# 10-TEST_PORT.net
KiCad netlist of a schematic drawn in Altium Designer
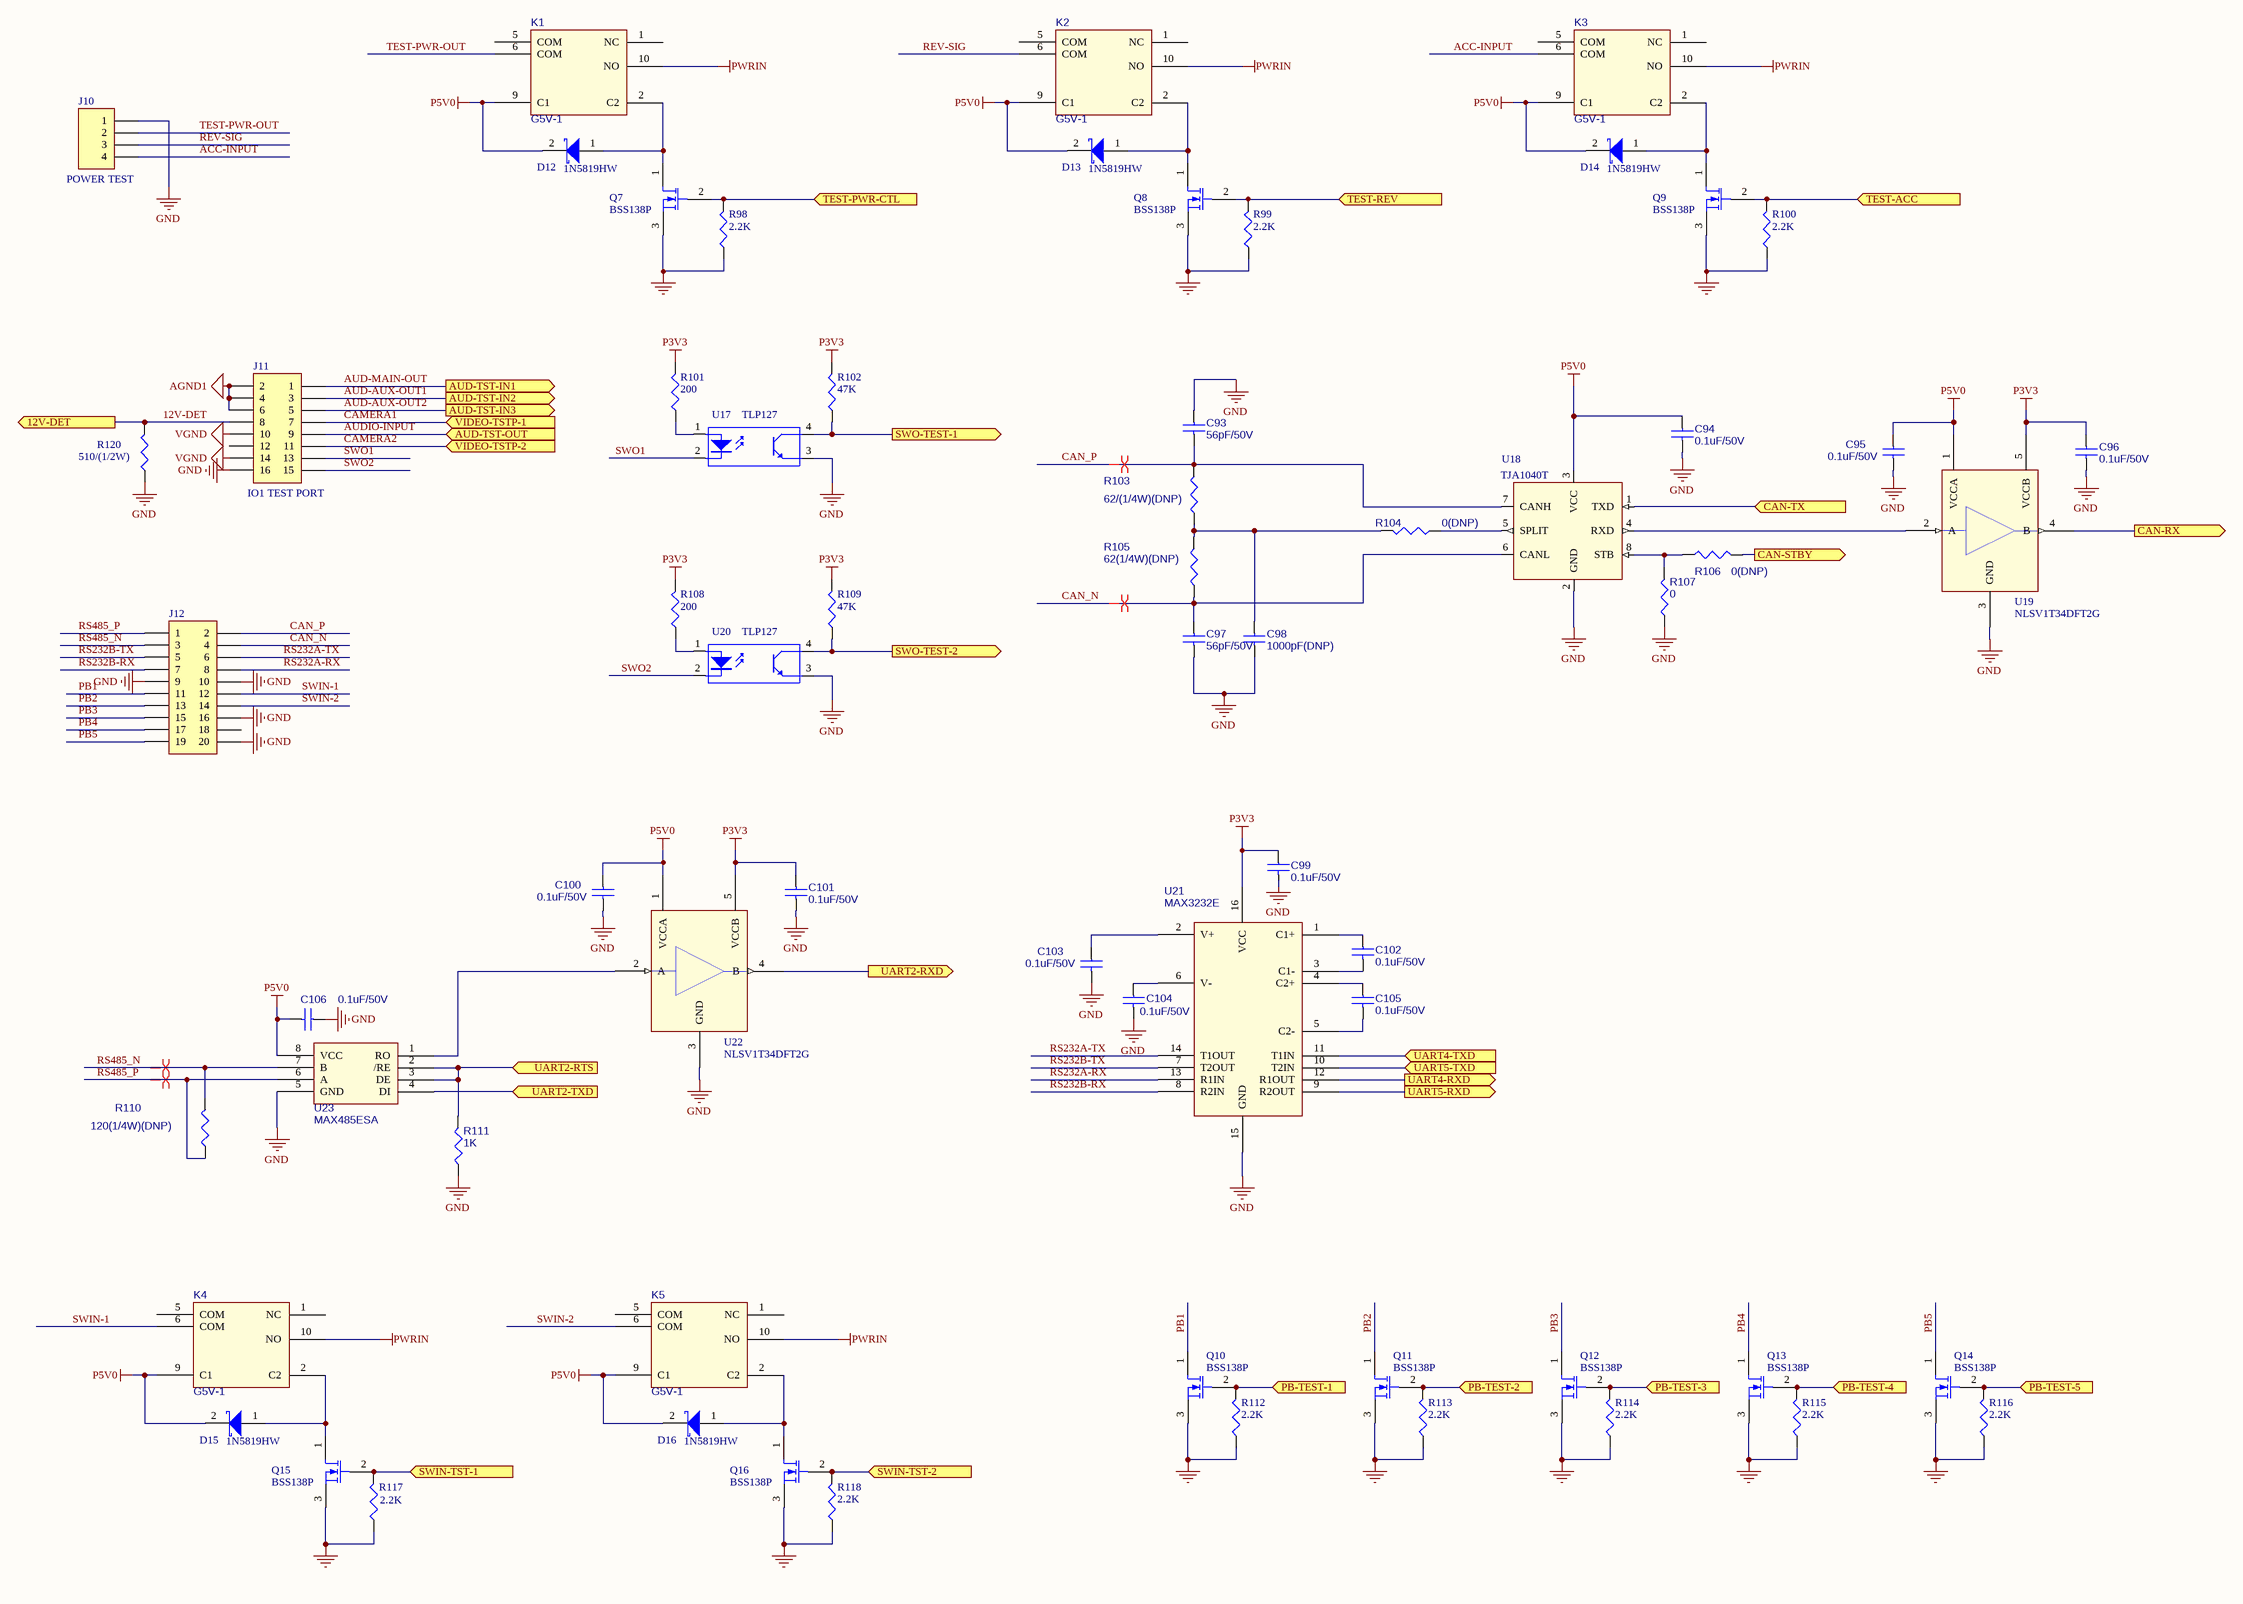
[diagram p0: 10-TEST_PORT.SchDoc]

(export (version "E")
  (design (tool "Eeschema 10.0.6"))
  (components
    (comp (ref "C93") (value "56pF/50V") (libsource (lib "*") (part "P_CAP NP")))
    (comp (ref "C94") (value "0.1uF/50V") (libsource (lib "*") (part "P_CAP NP")))
    (comp (ref "C95") (value "0.1uF/50V") (libsource (lib "*") (part "P_CAP NP")))
    (comp (ref "C96") (value "0.1uF/50V") (libsource (lib "*") (part "P_CAP NP")))
    (comp (ref "C97") (value "56pF/50V") (libsource (lib "*") (part "P_CAP NP")))
    (comp (ref "C98") (value "1000pF(DNP)") (libsource (lib "*") (part "P_CAP NP")))
    (comp (ref "C99") (value "0.1uF/50V") (libsource (lib "*") (part "CAP")))
    (comp (ref "C100") (value "0.1uF/50V") (libsource (lib "*") (part "P_CAP NP")))
    (comp (ref "C101") (value "0.1uF/50V") (libsource (lib "*") (part "P_CAP NP")))
    (comp (ref "C102") (value "0.1uF/50V") (libsource (lib "*") (part "CAP")))
    (comp (ref "C103") (value "0.1uF/50V") (libsource (lib "*") (part "CAP")))
    (comp (ref "C104") (value "0.1uF/50V") (libsource (lib "*") (part "CAP")))
    (comp (ref "C105") (value "0.1uF/50V") (libsource (lib "*") (part "CAP")))
    (comp (ref "C106")
      (value "0.1uF/50V")
      (fields (field (name "PART NUMBER") "SE132225K8L"))
      (libsource (lib "*") (part "P_CAP NP"))
    )
    (comp (ref "D12")
      (value "1N5819HW")
      (footprint "1N5819")
      (description "Schottky Rectifier")
      (libsource (lib "Miscellaneous Devices") (part "Diode 11DQ03"))
    )
    (comp (ref "D13")
      (value "1N5819HW")
      (footprint "1N5819")
      (description "Schottky Rectifier")
      (libsource (lib "Miscellaneous Devices") (part "Diode 11DQ03"))
    )
    (comp (ref "D14")
      (value "1N5819HW")
      (footprint "1N5819")
      (description "Schottky Rectifier")
      (libsource (lib "Miscellaneous Devices") (part "Diode 11DQ03"))
    )
    (comp (ref "D15")
      (value "1N5819HW")
      (footprint "1N5819")
      (description "Schottky Rectifier")
      (libsource (lib "Miscellaneous Devices") (part "Diode 11DQ03"))
    )
    (comp (ref "D16")
      (value "1N5819HW")
      (footprint "1N5819")
      (description "Schottky Rectifier")
      (libsource (lib "Miscellaneous Devices") (part "Diode 11DQ03"))
    )
    (comp (ref "J10")
      (value "POWER TEST")
      (footprint "3030WR-S-2*2P")
      (description "Header, 4-Pin")
      (fields (field (name "PUBLISHER") "Altium Limited"))
      (libsource (lib "Miscellaneous Connectors") (part "Header 4"))
    )
    (comp (ref "J11")
      (value "IO1 TEST PORT")
      (footprint "3030WR-S-2*8P")
      (description "Header, 8-Pin, Dual row")
      (fields (field (name "PUBLISHER") "Altium Limited"))
      (libsource (lib "Miscellaneous Connectors") (part "Header 8X2"))
    )
    (comp (ref "J12")
      (value "Header 10X2")
      (footprint "3030WR-S-2*10P")
      (description "Header, 10-Pin, Dual row")
      (fields (field (name "PUBLISHER") "Altium Limited"))
      (libsource (lib "Miscellaneous Connectors") (part "Header 10X2"))
    )
    (comp (ref "K1") (value "G5V-1") (libsource (lib "*") (part "G5V-1_0")))
    (comp (ref "K2") (value "G5V-1") (libsource (lib "*") (part "G5V-1_0")))
    (comp (ref "K3") (value "G5V-1") (libsource (lib "*") (part "G5V-1_0")))
    (comp (ref "K4") (value "G5V-1") (libsource (lib "*") (part "G5V-1_0")))
    (comp (ref "K5") (value "G5V-1") (libsource (lib "*") (part "G5V-1_0")))
    (comp (ref "Q7")
      (value "BSS138P")
      (footprint "NPN")
      (description "N-Channel MOSFET")
      (fields (field (name "PUBLISHER") "Altium Limited"))
      (libsource (lib "Miscellaneous Devices") (part "MOSFET-N"))
    )
    (comp (ref "Q8")
      (value "BSS138P")
      (footprint "NPN")
      (description "N-Channel MOSFET")
      (fields (field (name "PUBLISHER") "Altium Limited"))
      (libsource (lib "Miscellaneous Devices") (part "MOSFET-N"))
    )
    (comp (ref "Q9")
      (value "BSS138P")
      (footprint "NPN")
      (description "N-Channel MOSFET")
      (fields (field (name "PUBLISHER") "Altium Limited"))
      (libsource (lib "Miscellaneous Devices") (part "MOSFET-N"))
    )
    (comp (ref "Q10")
      (value "BSS138P")
      (footprint "NPN")
      (description "N-Channel MOSFET")
      (fields (field (name "PUBLISHER") "Altium Limited"))
      (libsource (lib "Miscellaneous Devices") (part "MOSFET-N"))
    )
    (comp (ref "Q11")
      (value "BSS138P")
      (footprint "NPN")
      (description "N-Channel MOSFET")
      (fields (field (name "PUBLISHER") "Altium Limited"))
      (libsource (lib "Miscellaneous Devices") (part "MOSFET-N"))
    )
    (comp (ref "Q12")
      (value "BSS138P")
      (footprint "NPN")
      (description "N-Channel MOSFET")
      (fields (field (name "PUBLISHER") "Altium Limited"))
      (libsource (lib "Miscellaneous Devices") (part "MOSFET-N"))
    )
    (comp (ref "Q13")
      (value "BSS138P")
      (footprint "NPN")
      (description "N-Channel MOSFET")
      (fields (field (name "PUBLISHER") "Altium Limited"))
      (libsource (lib "Miscellaneous Devices") (part "MOSFET-N"))
    )
    (comp (ref "Q14")
      (value "BSS138P")
      (footprint "NPN")
      (description "N-Channel MOSFET")
      (fields (field (name "PUBLISHER") "Altium Limited"))
      (libsource (lib "Miscellaneous Devices") (part "MOSFET-N"))
    )
    (comp (ref "Q15")
      (value "BSS138P")
      (footprint "NPN")
      (description "N-Channel MOSFET")
      (fields (field (name "PUBLISHER") "Altium Limited"))
      (libsource (lib "Miscellaneous Devices") (part "MOSFET-N"))
    )
    (comp (ref "Q16")
      (value "BSS138P")
      (footprint "NPN")
      (description "N-Channel MOSFET")
      (fields (field (name "PUBLISHER") "Altium Limited"))
      (libsource (lib "Miscellaneous Devices") (part "MOSFET-N"))
    )
    (comp (ref "R98")
      (value "2.2K")
      (footprint "0402")
      (description "Resistor")
      (fields (field (name "PUBLISHER") "Altium Limited"))
      (libsource (lib "Miscellaneous Devices") (part "Res3"))
    )
    (comp (ref "R99")
      (value "2.2K")
      (footprint "0402")
      (description "Resistor")
      (fields (field (name "PUBLISHER") "Altium Limited"))
      (libsource (lib "Miscellaneous Devices") (part "Res3"))
    )
    (comp (ref "R100")
      (value "2.2K")
      (footprint "0402")
      (description "Resistor")
      (fields (field (name "PUBLISHER") "Altium Limited"))
      (libsource (lib "Miscellaneous Devices") (part "Res3"))
    )
    (comp (ref "R101")
      (value "200")
      (footprint "0402")
      (description "Resistor")
      (fields (field (name "PUBLISHER") "Altium Limited"))
      (libsource (lib "Miscellaneous Devices") (part "Res3"))
    )
    (comp (ref "R102")
      (value "47K")
      (footprint "0402")
      (description "Resistor")
      (fields (field (name "PUBLISHER") "Altium Limited"))
      (libsource (lib "Miscellaneous Devices") (part "Res3"))
    )
    (comp (ref "R103") (value "62/(1/4W)(DNP)") (footprint "1206") (libsource (lib "*") (part "P_R")))
    (comp (ref "R104") (value "0(DNP)") (footprint "0402") (libsource (lib "*") (part "P_R")))
    (comp (ref "R105") (value "62(1/4W)(DNP)") (footprint "1206") (libsource (lib "*") (part "P_R")))
    (comp (ref "R106") (value "0(DNP)") (footprint "0402") (libsource (lib "*") (part "P_R")))
    (comp (ref "R107") (value "0") (footprint "0402") (libsource (lib "*") (part "P_R")))
    (comp (ref "R108")
      (value "200")
      (footprint "0402")
      (description "Resistor")
      (fields (field (name "PUBLISHER") "Altium Limited"))
      (libsource (lib "Miscellaneous Devices") (part "Res3"))
    )
    (comp (ref "R109")
      (value "47K")
      (footprint "0402")
      (description "Resistor")
      (fields (field (name "PUBLISHER") "Altium Limited"))
      (libsource (lib "Miscellaneous Devices") (part "Res3"))
    )
    (comp (ref "R110")
      (value "120(1/4W)(DNP)")
      (fields (field (name "PART NUMBER") "SD02810028L"))
      (libsource (lib "*") (part "R"))
    )
    (comp (ref "R111")
      (value "1K")
      (fields (field (name "PART NUMBER") "SD02810028L"))
      (libsource (lib "*") (part "R"))
    )
    (comp (ref "R112")
      (value "2.2K")
      (footprint "0402")
      (description "Resistor")
      (fields (field (name "PUBLISHER") "Altium Limited"))
      (libsource (lib "Miscellaneous Devices") (part "Res3"))
    )
    (comp (ref "R113")
      (value "2.2K")
      (footprint "0402")
      (description "Resistor")
      (fields (field (name "PUBLISHER") "Altium Limited"))
      (libsource (lib "Miscellaneous Devices") (part "Res3"))
    )
    (comp (ref "R114")
      (value "2.2K")
      (footprint "0402")
      (description "Resistor")
      (fields (field (name "PUBLISHER") "Altium Limited"))
      (libsource (lib "Miscellaneous Devices") (part "Res3"))
    )
    (comp (ref "R115")
      (value "2.2K")
      (footprint "0402")
      (description "Resistor")
      (fields (field (name "PUBLISHER") "Altium Limited"))
      (libsource (lib "Miscellaneous Devices") (part "Res3"))
    )
    (comp (ref "R116")
      (value "2.2K")
      (footprint "0402")
      (description "Resistor")
      (fields (field (name "PUBLISHER") "Altium Limited"))
      (libsource (lib "Miscellaneous Devices") (part "Res3"))
    )
    (comp (ref "R117")
      (value "2.2K")
      (footprint "0402")
      (description "Resistor")
      (fields (field (name "PUBLISHER") "Altium Limited"))
      (libsource (lib "Miscellaneous Devices") (part "Res3"))
    )
    (comp (ref "R118")
      (value "2.2K")
      (footprint "0402")
      (description "Resistor")
      (fields (field (name "PUBLISHER") "Altium Limited"))
      (libsource (lib "Miscellaneous Devices") (part "Res3"))
    )
    (comp (ref "R120")
      (value "510/(1/2W)")
      (footprint "1812")
      (description "Resistor")
      (fields (field (name "PUBLISHER") "Altium Limited"))
      (libsource (lib "Miscellaneous Devices") (part "Res3"))
    )
    (comp (ref "U17")
      (value "TLP127")
      (footprint "TLP127")
      (description "4-Pin Phototransistor Optocoupler")
      (fields (field (name "PUBLISHER") "Altium Limited"))
      (libsource (lib "Miscellaneous Devices") (part "Optoisolator1"))
    )
    (comp (ref "U18")
      (value "TJA1040T")
      (footprint "SO8")
      (description "IC XCVR CAN HS 5V SO8")
      (libsource (lib "*") (part "TJA1040T_SO_8P"))
    )
    (comp (ref "U19")
      (value "NLSV1T34DFT2G")
      (footprint "SC70")
      (libsource (lib "Schlib") (part "NLSV1T34DFT2G"))
    )
    (comp (ref "U20")
      (value "TLP127")
      (footprint "TLP127")
      (description "4-Pin Phototransistor Optocoupler")
      (fields (field (name "PUBLISHER") "Altium Limited"))
      (libsource (lib "Miscellaneous Devices") (part "Optoisolator1"))
    )
    (comp (ref "U21") (value "MAX3232E") (footprint "SO-16") (libsource (lib "*") (part "MAX3232")))
    (comp (ref "U22")
      (value "NLSV1T34DFT2G")
      (footprint "SC70")
      (libsource (lib "Schlib") (part "NLSV1T34DFT2G"))
    )
    (comp (ref "U23") (value "MAX485ESA") (libsource (lib "*") (part "MAX485")))
  )
  (nets
    (net (code "1") (name "/12V-DET") (class "Default")
      (node (ref "J11") (pin "8") (pinfunction "8_8") (pintype "passive"))
      (node (ref "R120") (pin "1") (pinfunction "1_1") (pintype "passive"))
    )
    (net (code "2") (name "/ACC-INPUT") (class "Default")
      (node (ref "J10") (pin "4") (pinfunction "4_4") (pintype "passive"))
      (node (ref "K3") (pin "6") (pinfunction "COM_6") (pintype "power_in"))
    )
    (net (code "3") (name "/AUD-AUX-OUT1") (class "Default")
      (node (ref "J11") (pin "3") (pinfunction "3_3") (pintype "passive"))
    )
    (net (code "4") (name "/AUD-AUX-OUT2") (class "Default")
      (node (ref "J11") (pin "5") (pinfunction "5_5") (pintype "passive"))
    )
    (net (code "5") (name "/AUD-MAIN-OUT") (class "Default")
      (node (ref "J11") (pin "1") (pinfunction "1_1") (pintype "passive"))
    )
    (net (code "6") (name "/AUDIO-INPUT") (class "Default")
      (node (ref "J11") (pin "9") (pinfunction "9_9") (pintype "passive"))
    )
    (net (code "7") (name "/CAMERA1") (class "Default")
      (node (ref "J11") (pin "7") (pinfunction "7_7") (pintype "passive"))
    )
    (net (code "8") (name "/CAMERA2") (class "Default")
      (node (ref "J11") (pin "11") (pinfunction "11_11") (pintype "passive"))
    )
    (net (code "9") (name "/CAN-RX") (class "Default")
      (node (ref "U19") (pin "4") (pinfunction "B_4") (pintype "output"))
    )
    (net (code "10") (name "/CAN-STBY") (class "Default")
      (node (ref "R106") (pin "1") (pinfunction "1_1") (pintype "passive"))
    )
    (net (code "11") (name "/CAN-TX") (class "Default")
      (node (ref "U18") (pin "1") (pinfunction "TXD_1") (pintype "input"))
    )
    (net (code "12") (name "/CAN_N") (class "Default")
      (node (ref "C97") (pin "1") (pinfunction "1_1") (pintype "passive"))
      (node (ref "J12") (pin "4") (pinfunction "4_4") (pintype "passive"))
      (node (ref "R105") (pin "2") (pinfunction "2_2") (pintype "passive"))
      (node (ref "U18") (pin "6") (pinfunction "CANL_6") (pintype "bidirectional"))
    )
    (net (code "13") (name "/CAN_P") (class "Default")
      (node (ref "C93") (pin "2") (pinfunction "2_2") (pintype "passive"))
      (node (ref "J12") (pin "2") (pinfunction "2_2") (pintype "passive"))
      (node (ref "R103") (pin "1") (pinfunction "1_1") (pintype "passive"))
      (node (ref "U18") (pin "7") (pinfunction "CANH_7") (pintype "bidirectional"))
    )
    (net (code "14") (name "/PB-TEST-1") (class "Default")
      (node (ref "Q10") (pin "2") (pinfunction "G_2") (pintype "passive"))
      (node (ref "R112") (pin "1") (pinfunction "1_1") (pintype "passive"))
    )
    (net (code "15") (name "/PB-TEST-2") (class "Default")
      (node (ref "Q11") (pin "2") (pinfunction "G_2") (pintype "passive"))
      (node (ref "R113") (pin "1") (pinfunction "1_1") (pintype "passive"))
    )
    (net (code "16") (name "/PB-TEST-3") (class "Default")
      (node (ref "Q12") (pin "2") (pinfunction "G_2") (pintype "passive"))
      (node (ref "R114") (pin "1") (pinfunction "1_1") (pintype "passive"))
    )
    (net (code "17") (name "/PB-TEST-4") (class "Default")
      (node (ref "Q13") (pin "2") (pinfunction "G_2") (pintype "passive"))
      (node (ref "R115") (pin "1") (pinfunction "1_1") (pintype "passive"))
    )
    (net (code "18") (name "/PB-TEST-5") (class "Default")
      (node (ref "Q14") (pin "2") (pinfunction "G_2") (pintype "passive"))
      (node (ref "R116") (pin "1") (pinfunction "1_1") (pintype "passive"))
    )
    (net (code "19") (name "/PB1") (class "Default")
      (node (ref "J12") (pin "11") (pinfunction "11_11") (pintype "passive"))
      (node (ref "Q10") (pin "1") (pinfunction "D_1") (pintype "passive"))
    )
    (net (code "20") (name "/PB2") (class "Default")
      (node (ref "J12") (pin "13") (pinfunction "13_13") (pintype "passive"))
      (node (ref "Q11") (pin "1") (pinfunction "D_1") (pintype "passive"))
    )
    (net (code "21") (name "/PB3") (class "Default")
      (node (ref "J12") (pin "15") (pinfunction "15_15") (pintype "passive"))
      (node (ref "Q12") (pin "1") (pinfunction "D_1") (pintype "passive"))
    )
    (net (code "22") (name "/PB4") (class "Default")
      (node (ref "J12") (pin "17") (pinfunction "17_17") (pintype "passive"))
      (node (ref "Q13") (pin "1") (pinfunction "D_1") (pintype "passive"))
    )
    (net (code "23") (name "/PB5") (class "Default")
      (node (ref "J12") (pin "19") (pinfunction "19_19") (pintype "passive"))
      (node (ref "Q14") (pin "1") (pinfunction "D_1") (pintype "passive"))
    )
    (net (code "24") (name "/REV-SIG") (class "Default")
      (node (ref "J10") (pin "3") (pinfunction "3_3") (pintype "passive"))
      (node (ref "K2") (pin "6") (pinfunction "COM_6") (pintype "power_in"))
    )
    (net (code "25") (name "/RS232A-RX") (class "Default")
      (node (ref "J12") (pin "8") (pinfunction "8_8") (pintype "passive"))
      (node (ref "U21") (pin "13") (pinfunction "R1IN_13") (pintype "passive"))
    )
    (net (code "26") (name "/RS232A-TX") (class "Default")
      (node (ref "J12") (pin "6") (pinfunction "6_6") (pintype "passive"))
      (node (ref "U21") (pin "14") (pinfunction "T1OUT_14") (pintype "passive"))
    )
    (net (code "27") (name "/RS232B-RX") (class "Default")
      (node (ref "J12") (pin "7") (pinfunction "7_7") (pintype "passive"))
      (node (ref "U21") (pin "8") (pinfunction "R2IN_8") (pintype "passive"))
    )
    (net (code "28") (name "/RS232B-TX") (class "Default")
      (node (ref "J12") (pin "5") (pinfunction "5_5") (pintype "passive"))
      (node (ref "U21") (pin "7") (pinfunction "T2OUT_7") (pintype "passive"))
    )
    (net (code "29") (name "/RS485_N") (class "Default")
      (node (ref "J12") (pin "3") (pinfunction "3_3") (pintype "passive"))
      (node (ref "R110") (pin "1") (pinfunction "1_1") (pintype "passive"))
      (node (ref "U23") (pin "7") (pinfunction "B_7") (pintype "passive"))
    )
    (net (code "30") (name "/RS485_P") (class "Default")
      (node (ref "J12") (pin "1") (pinfunction "1_1") (pintype "passive"))
      (node (ref "R110") (pin "2") (pinfunction "2_2") (pintype "passive"))
      (node (ref "U23") (pin "6") (pinfunction "A_6") (pintype "passive"))
    )
    (net (code "31") (name "/SWIN-1") (class "Default")
      (node (ref "J12") (pin "12") (pinfunction "12_12") (pintype "passive"))
      (node (ref "K4") (pin "6") (pinfunction "COM_6") (pintype "power_in"))
    )
    (net (code "32") (name "/SWIN-2") (class "Default")
      (node (ref "J12") (pin "14") (pinfunction "14_14") (pintype "passive"))
      (node (ref "K5") (pin "6") (pinfunction "COM_6") (pintype "power_in"))
    )
    (net (code "33") (name "/SWIN-TST-1") (class "Default")
      (node (ref "Q15") (pin "2") (pinfunction "G_2") (pintype "passive"))
      (node (ref "R117") (pin "1") (pinfunction "1_1") (pintype "passive"))
    )
    (net (code "34") (name "/SWIN-TST-2") (class "Default")
      (node (ref "Q16") (pin "2") (pinfunction "G_2") (pintype "passive"))
      (node (ref "R118") (pin "1") (pinfunction "1_1") (pintype "passive"))
    )
    (net (code "35") (name "/SWO-TEST-1") (class "Default")
      (node (ref "R102") (pin "2") (pinfunction "2_2") (pintype "passive"))
      (node (ref "U17") (pin "4") (pinfunction "C_4") (pintype "passive"))
    )
    (net (code "36") (name "/SWO-TEST-2") (class "Default")
      (node (ref "R109") (pin "2") (pinfunction "2_2") (pintype "passive"))
      (node (ref "U20") (pin "4") (pinfunction "C_4") (pintype "passive"))
    )
    (net (code "37") (name "/SWO1") (class "Default")
      (node (ref "J11") (pin "13") (pinfunction "13_13") (pintype "passive"))
      (node (ref "U17") (pin "2") (pinfunction "K_2") (pintype "passive"))
    )
    (net (code "38") (name "/SWO2") (class "Default")
      (node (ref "J11") (pin "15") (pinfunction "15_15") (pintype "passive"))
      (node (ref "U20") (pin "2") (pinfunction "K_2") (pintype "passive"))
    )
    (net (code "39") (name "/TEST-ACC") (class "Default")
      (node (ref "Q9") (pin "2") (pinfunction "G_2") (pintype "passive"))
      (node (ref "R100") (pin "1") (pinfunction "1_1") (pintype "passive"))
    )
    (net (code "40") (name "/TEST-PWR-CTL") (class "Default")
      (node (ref "Q7") (pin "2") (pinfunction "G_2") (pintype "passive"))
      (node (ref "R98") (pin "1") (pinfunction "1_1") (pintype "passive"))
    )
    (net (code "41") (name "/TEST-PWR-OUT") (class "Default")
      (node (ref "J10") (pin "2") (pinfunction "2_2") (pintype "passive"))
      (node (ref "K1") (pin "6") (pinfunction "COM_6") (pintype "power_in"))
    )
    (net (code "42") (name "/TEST-REV") (class "Default")
      (node (ref "Q8") (pin "2") (pinfunction "G_2") (pintype "passive"))
      (node (ref "R99") (pin "1") (pinfunction "1_1") (pintype "passive"))
    )
    (net (code "43") (name "/UART2-RTS") (class "Default")
      (node (ref "R111") (pin "1") (pinfunction "1_1") (pintype "passive"))
      (node (ref "U23") (pin "2") (pinfunction "/RE_2") (pintype "passive"))
      (node (ref "U23") (pin "3") (pinfunction "DE_3") (pintype "passive"))
    )
    (net (code "44") (name "/UART2-RXD") (class "Default")
      (node (ref "U22") (pin "4") (pinfunction "B_4") (pintype "output"))
    )
    (net (code "45") (name "/UART2-TXD") (class "Default")
      (node (ref "U23") (pin "4") (pinfunction "DI_4") (pintype "passive"))
    )
    (net (code "46") (name "/UART4-RXD") (class "Default")
      (node (ref "U21") (pin "12") (pinfunction "R1OUT_12") (pintype "passive"))
    )
    (net (code "47") (name "/UART4-TXD") (class "Default")
      (node (ref "U21") (pin "11") (pinfunction "T1IN_11") (pintype "passive"))
    )
    (net (code "48") (name "/UART5-RXD") (class "Default")
      (node (ref "U21") (pin "9") (pinfunction "R2OUT_9") (pintype "passive"))
    )
    (net (code "49") (name "/UART5-TXD") (class "Default")
      (node (ref "U21") (pin "10") (pinfunction "T2IN_10") (pintype "passive"))
    )
    (net (code "50") (name "AGND1") (class "Default")
      (node (ref "J11") (pin "2") (pinfunction "2_2") (pintype "passive"))
      (node (ref "J11") (pin "4") (pinfunction "4_4") (pintype "passive"))
      (node (ref "J11") (pin "6") (pinfunction "6_6") (pintype "passive"))
    )
    (net (code "51") (name "GND") (class "Default")
      (node (ref "C100") (pin "2") (pinfunction "2_2") (pintype "passive"))
      (node (ref "C101") (pin "2") (pinfunction "2_2") (pintype "passive"))
      (node (ref "C103") (pin "2") (pinfunction "2_2") (pintype "passive"))
      (node (ref "C104") (pin "2") (pinfunction "2_2") (pintype "passive"))
      (node (ref "C106") (pin "1") (pinfunction "1_1") (pintype "passive"))
      (node (ref "C93") (pin "1") (pinfunction "1_1") (pintype "passive"))
      (node (ref "C94") (pin "2") (pinfunction "2_2") (pintype "passive"))
      (node (ref "C95") (pin "2") (pinfunction "2_2") (pintype "passive"))
      (node (ref "C96") (pin "2") (pinfunction "2_2") (pintype "passive"))
      (node (ref "C97") (pin "2") (pinfunction "2_2") (pintype "passive"))
      (node (ref "C98") (pin "2") (pinfunction "2_2") (pintype "passive"))
      (node (ref "C99") (pin "2") (pinfunction "2_2") (pintype "passive"))
      (node (ref "J10") (pin "1") (pinfunction "1_1") (pintype "passive"))
      (node (ref "J11") (pin "16") (pinfunction "16_16") (pintype "passive"))
      (node (ref "J12") (pin "10") (pinfunction "10_10") (pintype "passive"))
      (node (ref "J12") (pin "16") (pinfunction "16_16") (pintype "passive"))
      (node (ref "J12") (pin "20") (pinfunction "20_20") (pintype "passive"))
      (node (ref "J12") (pin "9") (pinfunction "9_9") (pintype "passive"))
      (node (ref "Q10") (pin "3") (pinfunction "S_3") (pintype "passive"))
      (node (ref "Q11") (pin "3") (pinfunction "S_3") (pintype "passive"))
      (node (ref "Q12") (pin "3") (pinfunction "S_3") (pintype "passive"))
      (node (ref "Q13") (pin "3") (pinfunction "S_3") (pintype "passive"))
      (node (ref "Q14") (pin "3") (pinfunction "S_3") (pintype "passive"))
      (node (ref "Q15") (pin "3") (pinfunction "S_3") (pintype "passive"))
      (node (ref "Q16") (pin "3") (pinfunction "S_3") (pintype "passive"))
      (node (ref "Q7") (pin "3") (pinfunction "S_3") (pintype "passive"))
      (node (ref "Q8") (pin "3") (pinfunction "S_3") (pintype "passive"))
      (node (ref "Q9") (pin "3") (pinfunction "S_3") (pintype "passive"))
      (node (ref "R100") (pin "2") (pinfunction "2_2") (pintype "passive"))
      (node (ref "R107") (pin "2") (pinfunction "2_2") (pintype "passive"))
      (node (ref "R111") (pin "2") (pinfunction "2_2") (pintype "passive"))
      (node (ref "R112") (pin "2") (pinfunction "2_2") (pintype "passive"))
      (node (ref "R113") (pin "2") (pinfunction "2_2") (pintype "passive"))
      (node (ref "R114") (pin "2") (pinfunction "2_2") (pintype "passive"))
      (node (ref "R115") (pin "2") (pinfunction "2_2") (pintype "passive"))
      (node (ref "R116") (pin "2") (pinfunction "2_2") (pintype "passive"))
      (node (ref "R117") (pin "2") (pinfunction "2_2") (pintype "passive"))
      (node (ref "R118") (pin "2") (pinfunction "2_2") (pintype "passive"))
      (node (ref "R120") (pin "2") (pinfunction "2_2") (pintype "passive"))
      (node (ref "R98") (pin "2") (pinfunction "2_2") (pintype "passive"))
      (node (ref "R99") (pin "2") (pinfunction "2_2") (pintype "passive"))
      (node (ref "U17") (pin "3") (pinfunction "E_3") (pintype "passive"))
      (node (ref "U18") (pin "2") (pinfunction "GND_2") (pintype "power_in"))
      (node (ref "U19") (pin "3") (pinfunction "GND_3") (pintype "power_in"))
      (node (ref "U20") (pin "3") (pinfunction "E_3") (pintype "passive"))
      (node (ref "U21") (pin "15") (pinfunction "GND_15") (pintype "passive"))
      (node (ref "U22") (pin "3") (pinfunction "GND_3") (pintype "power_in"))
      (node (ref "U23") (pin "5") (pinfunction "GND_5") (pintype "passive"))
    )
    (net (code "52") (name "Net-(C98-Pad1)") (class "Default")
      (node (ref "C98") (pin "1") (pinfunction "1_1") (pintype "passive"))
      (node (ref "R103") (pin "2") (pinfunction "2_2") (pintype "passive"))
      (node (ref "R104") (pin "1") (pinfunction "1_1") (pintype "passive"))
      (node (ref "R105") (pin "1") (pinfunction "1_1") (pintype "passive"))
    )
    (net (code "53") (name "Net-(D12-A)") (class "Default")
      (node (ref "D12") (pin "1") (pinfunction "A_1") (pintype "passive"))
      (node (ref "K1") (pin "2") (pinfunction "C2_2") (pintype "passive"))
      (node (ref "Q7") (pin "1") (pinfunction "D_1") (pintype "passive"))
    )
    (net (code "54") (name "Net-(D13-A)") (class "Default")
      (node (ref "D13") (pin "1") (pinfunction "A_1") (pintype "passive"))
      (node (ref "K2") (pin "2") (pinfunction "C2_2") (pintype "passive"))
      (node (ref "Q8") (pin "1") (pinfunction "D_1") (pintype "passive"))
    )
    (net (code "55") (name "Net-(D14-A)") (class "Default")
      (node (ref "D14") (pin "1") (pinfunction "A_1") (pintype "passive"))
      (node (ref "K3") (pin "2") (pinfunction "C2_2") (pintype "passive"))
      (node (ref "Q9") (pin "1") (pinfunction "D_1") (pintype "passive"))
    )
    (net (code "56") (name "Net-(D15-A)") (class "Default")
      (node (ref "D15") (pin "1") (pinfunction "A_1") (pintype "passive"))
      (node (ref "K4") (pin "2") (pinfunction "C2_2") (pintype "passive"))
      (node (ref "Q15") (pin "1") (pinfunction "D_1") (pintype "passive"))
    )
    (net (code "57") (name "Net-(D16-A)") (class "Default")
      (node (ref "D16") (pin "1") (pinfunction "A_1") (pintype "passive"))
      (node (ref "K5") (pin "2") (pinfunction "C2_2") (pintype "passive"))
      (node (ref "Q16") (pin "1") (pinfunction "D_1") (pintype "passive"))
    )
    (net (code "58") (name "Net-(U17-A)") (class "Default")
      (node (ref "R101") (pin "2") (pinfunction "2_2") (pintype "passive"))
      (node (ref "U17") (pin "1") (pinfunction "A_1") (pintype "passive"))
    )
    (net (code "59") (name "Net-(U18-RXD)") (class "Default")
      (node (ref "U18") (pin "4") (pinfunction "RXD_4") (pintype "output"))
      (node (ref "U19") (pin "2") (pinfunction "A_2") (pintype "input"))
    )
    (net (code "60") (name "Net-(U18-SPLIT)") (class "Default")
      (node (ref "R104") (pin "2") (pinfunction "2_2") (pintype "passive"))
      (node (ref "U18") (pin "5") (pinfunction "SPLIT_5") (pintype "output"))
    )
    (net (code "61") (name "Net-(U18-STB)") (class "Default")
      (node (ref "R106") (pin "2") (pinfunction "2_2") (pintype "passive"))
      (node (ref "R107") (pin "1") (pinfunction "1_1") (pintype "passive"))
      (node (ref "U18") (pin "8") (pinfunction "STB_8") (pintype "input"))
    )
    (net (code "62") (name "Net-(U20-A)") (class "Default")
      (node (ref "R108") (pin "2") (pinfunction "2_2") (pintype "passive"))
      (node (ref "U20") (pin "1") (pinfunction "A_1") (pintype "passive"))
    )
    (net (code "63") (name "Net-(U21-C1+)") (class "Default")
      (node (ref "C102") (pin "1") (pinfunction "1_1") (pintype "passive"))
      (node (ref "U21") (pin "1") (pinfunction "C1+_1") (pintype "passive"))
    )
    (net (code "64") (name "Net-(U21-C1-)") (class "Default")
      (node (ref "C102") (pin "2") (pinfunction "2_2") (pintype "passive"))
      (node (ref "U21") (pin "3") (pinfunction "C1-_3") (pintype "passive"))
    )
    (net (code "65") (name "Net-(U21-C2+)") (class "Default")
      (node (ref "C105") (pin "1") (pinfunction "1_1") (pintype "passive"))
      (node (ref "U21") (pin "4") (pinfunction "C2+_4") (pintype "passive"))
    )
    (net (code "66") (name "Net-(U21-C2-)") (class "Default")
      (node (ref "C105") (pin "2") (pinfunction "2_2") (pintype "passive"))
      (node (ref "U21") (pin "5") (pinfunction "C2-_5") (pintype "passive"))
    )
    (net (code "67") (name "Net-(U21-V+)") (class "Default")
      (node (ref "C103") (pin "1") (pinfunction "1_1") (pintype "passive"))
      (node (ref "U21") (pin "2") (pinfunction "V+_2") (pintype "passive"))
    )
    (net (code "68") (name "Net-(U21-V-)") (class "Default")
      (node (ref "C104") (pin "1") (pinfunction "1_1") (pintype "passive"))
      (node (ref "U21") (pin "6") (pinfunction "V-_6") (pintype "passive"))
    )
    (net (code "69") (name "Net-(U22-A)") (class "Default")
      (node (ref "U22") (pin "2") (pinfunction "A_2") (pintype "input"))
      (node (ref "U23") (pin "1") (pinfunction "RO_1") (pintype "passive"))
    )
    (net (code "70") (name "P3V3") (class "Default")
      (node (ref "C101") (pin "1") (pinfunction "1_1") (pintype "passive"))
      (node (ref "C96") (pin "1") (pinfunction "1_1") (pintype "passive"))
      (node (ref "C99") (pin "1") (pinfunction "1_1") (pintype "passive"))
      (node (ref "R101") (pin "1") (pinfunction "1_1") (pintype "passive"))
      (node (ref "R102") (pin "1") (pinfunction "1_1") (pintype "passive"))
      (node (ref "R108") (pin "1") (pinfunction "1_1") (pintype "passive"))
      (node (ref "R109") (pin "1") (pinfunction "1_1") (pintype "passive"))
      (node (ref "U19") (pin "5") (pinfunction "VCCB_5") (pintype "power_in"))
      (node (ref "U21") (pin "16") (pinfunction "VCC_16") (pintype "passive"))
      (node (ref "U22") (pin "5") (pinfunction "VCCB_5") (pintype "power_in"))
    )
    (net (code "71") (name "P5V0") (class "Default")
      (node (ref "C100") (pin "1") (pinfunction "1_1") (pintype "passive"))
      (node (ref "C106") (pin "2") (pinfunction "2_2") (pintype "passive"))
      (node (ref "C94") (pin "1") (pinfunction "1_1") (pintype "passive"))
      (node (ref "C95") (pin "1") (pinfunction "1_1") (pintype "passive"))
      (node (ref "D12") (pin "2") (pinfunction "K_2") (pintype "passive"))
      (node (ref "D13") (pin "2") (pinfunction "K_2") (pintype "passive"))
      (node (ref "D14") (pin "2") (pinfunction "K_2") (pintype "passive"))
      (node (ref "D15") (pin "2") (pinfunction "K_2") (pintype "passive"))
      (node (ref "D16") (pin "2") (pinfunction "K_2") (pintype "passive"))
      (node (ref "K1") (pin "9") (pinfunction "C1_9") (pintype "passive"))
      (node (ref "K2") (pin "9") (pinfunction "C1_9") (pintype "passive"))
      (node (ref "K3") (pin "9") (pinfunction "C1_9") (pintype "passive"))
      (node (ref "K4") (pin "9") (pinfunction "C1_9") (pintype "passive"))
      (node (ref "K5") (pin "9") (pinfunction "C1_9") (pintype "passive"))
      (node (ref "U18") (pin "3") (pinfunction "VCC_3") (pintype "power_in"))
      (node (ref "U19") (pin "1") (pinfunction "VCCA_1") (pintype "power_in"))
      (node (ref "U22") (pin "1") (pinfunction "VCCA_1") (pintype "power_in"))
      (node (ref "U23") (pin "8") (pinfunction "VCC_8") (pintype "passive"))
    )
    (net (code "72") (name "PWRIN") (class "Default")
      (node (ref "K1") (pin "10") (pinfunction "NO_10") (pintype "passive"))
      (node (ref "K2") (pin "10") (pinfunction "NO_10") (pintype "passive"))
      (node (ref "K3") (pin "10") (pinfunction "NO_10") (pintype "passive"))
      (node (ref "K4") (pin "10") (pinfunction "NO_10") (pintype "passive"))
      (node (ref "K5") (pin "10") (pinfunction "NO_10") (pintype "passive"))
    )
    (net (code "73") (name "VGND") (class "Default")
      (node (ref "J11") (pin "10") (pinfunction "10_10") (pintype "passive"))
      (node (ref "J11") (pin "14") (pinfunction "14_14") (pintype "passive"))
    )
    (net (code "74") (name "unconnected-(J11-Pad12)") (class "Default")
      (node (ref "J11") (pin "12") (pinfunction "12_12") (pintype "passive"))
    )
    (net (code "75") (name "unconnected-(J12-Pad18)") (class "Default")
      (node (ref "J12") (pin "18") (pinfunction "18_18") (pintype "passive"))
    )
    (net (code "76") (name "unconnected-(K1-COM-Pad5)") (class "Default")
      (node (ref "K1") (pin "5") (pinfunction "COM_5") (pintype "power_in"))
    )
    (net (code "77") (name "unconnected-(K1-NC-Pad1)") (class "Default")
      (node (ref "K1") (pin "1") (pinfunction "NC_1") (pintype "passive"))
    )
    (net (code "78") (name "unconnected-(K2-COM-Pad5)") (class "Default")
      (node (ref "K2") (pin "5") (pinfunction "COM_5") (pintype "power_in"))
    )
    (net (code "79") (name "unconnected-(K2-NC-Pad1)") (class "Default")
      (node (ref "K2") (pin "1") (pinfunction "NC_1") (pintype "passive"))
    )
    (net (code "80") (name "unconnected-(K3-COM-Pad5)") (class "Default")
      (node (ref "K3") (pin "5") (pinfunction "COM_5") (pintype "power_in"))
    )
    (net (code "81") (name "unconnected-(K3-NC-Pad1)") (class "Default")
      (node (ref "K3") (pin "1") (pinfunction "NC_1") (pintype "passive"))
    )
    (net (code "82") (name "unconnected-(K4-COM-Pad5)") (class "Default")
      (node (ref "K4") (pin "5") (pinfunction "COM_5") (pintype "power_in"))
    )
    (net (code "83") (name "unconnected-(K4-NC-Pad1)") (class "Default")
      (node (ref "K4") (pin "1") (pinfunction "NC_1") (pintype "passive"))
    )
    (net (code "84") (name "unconnected-(K5-COM-Pad5)") (class "Default")
      (node (ref "K5") (pin "5") (pinfunction "COM_5") (pintype "power_in"))
    )
    (net (code "85") (name "unconnected-(K5-NC-Pad1)") (class "Default")
      (node (ref "K5") (pin "1") (pinfunction "NC_1") (pintype "passive"))
    )
  )
)
